# Andonstar_LED_Ring.net
KiCad netlist of a schematic drawn in EAGLE
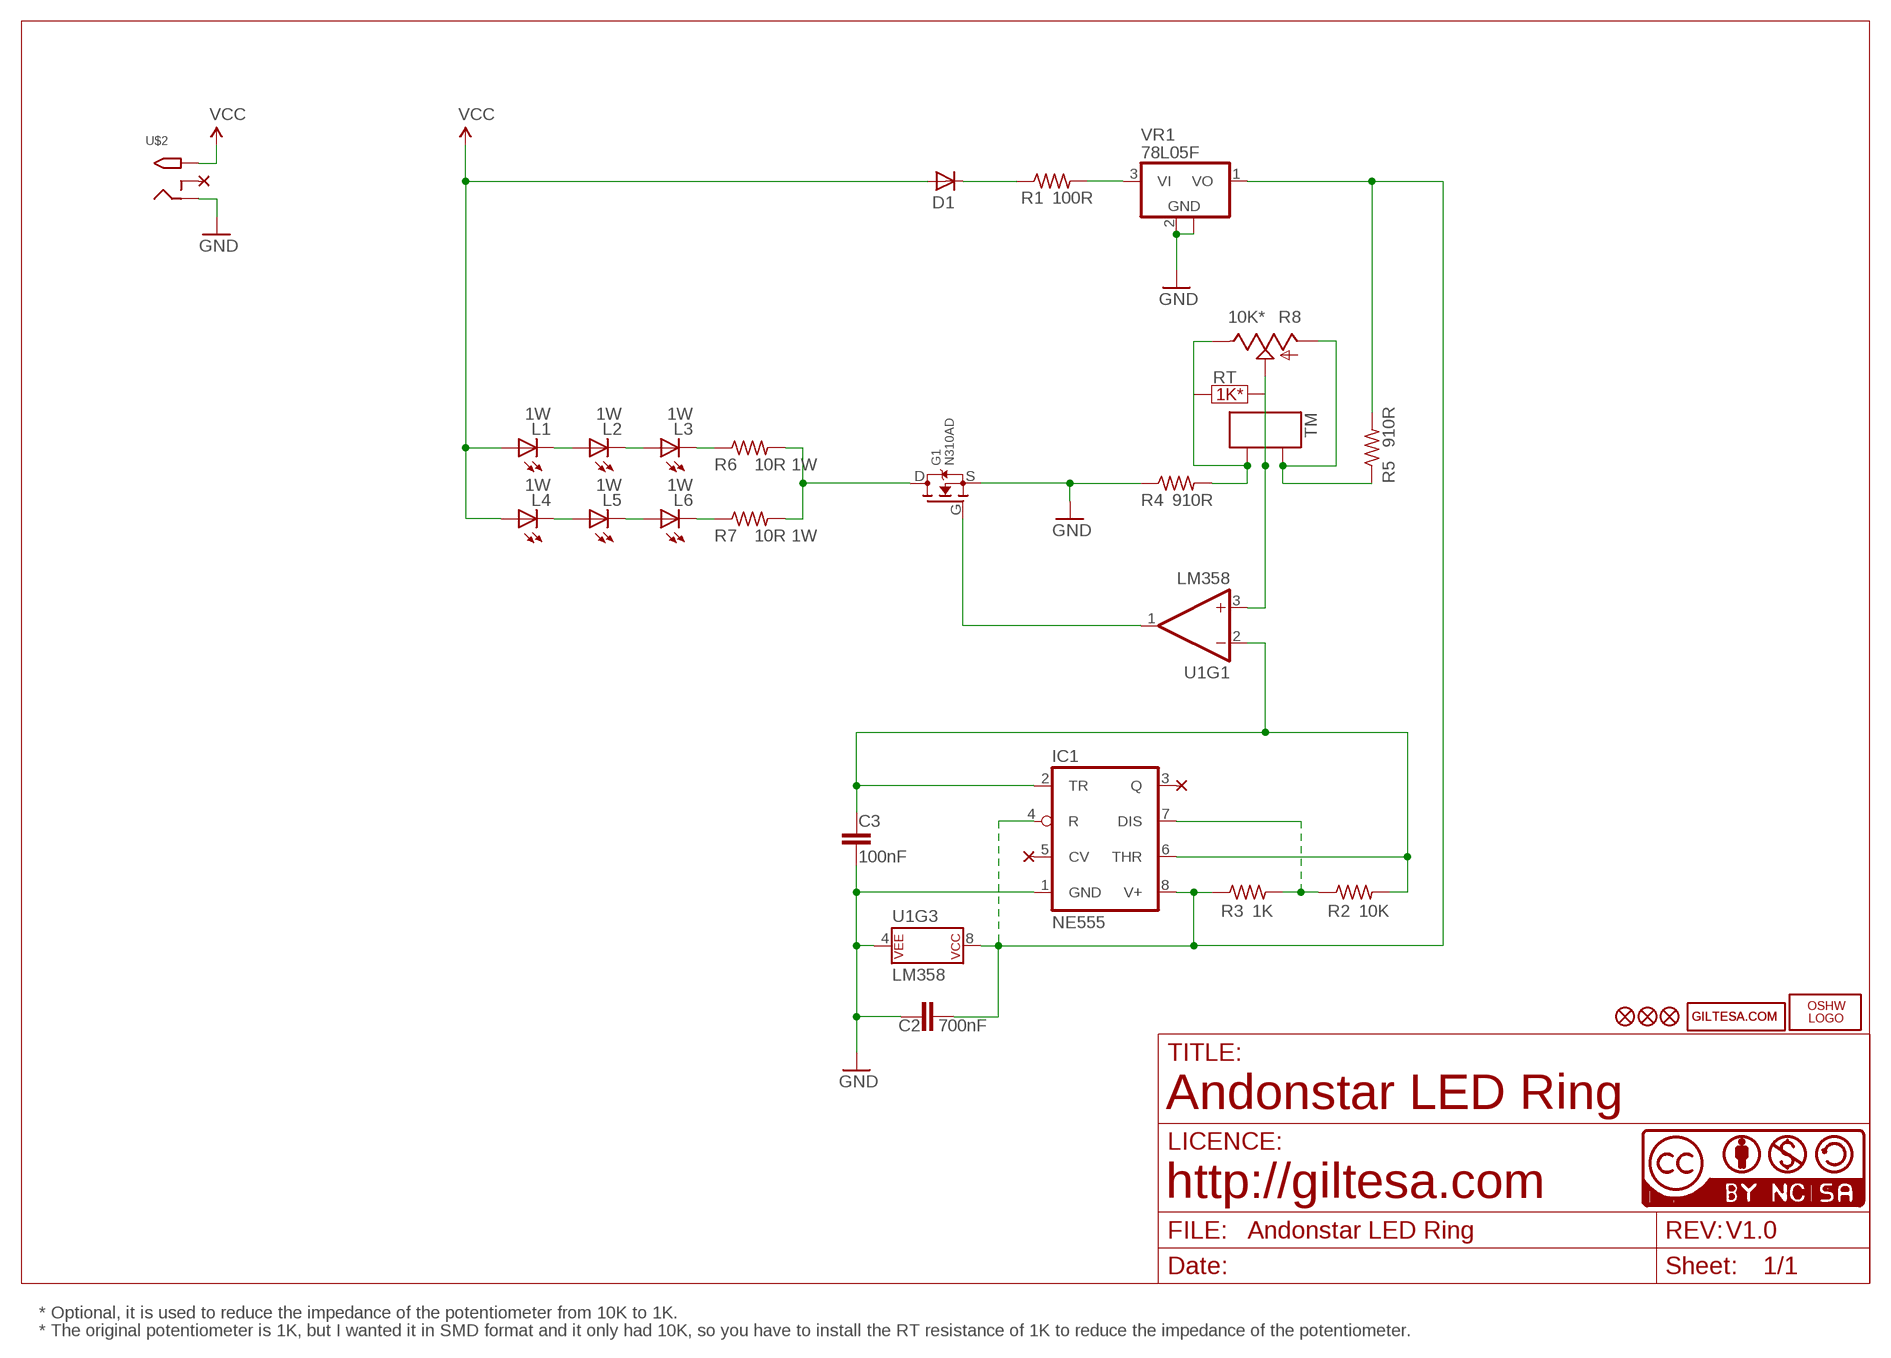
[diagram p0: schematic, sheet 1]

(export (version "E")
  (design (tool "Eeschema 10.0.6"))
  (components
    (comp (ref "C2")
      (value "700nF")
      (footprint "eagle-import:C0603")
      (libsource (lib "eagle-import") (part "C0603"))
    )
    (comp (ref "C3")
      (value "100nF")
      (footprint "eagle-import:C0603")
      (libsource (lib "eagle-import") (part "C0603"))
    )
    (comp (ref "D1")
      (value "DIODE-GF1")
      (footprint "eagle-import:GF1")
      (libsource (lib "eagle-import") (part "DIODE-GF1"))
    )
    (comp (ref "G1")
      (value "N310AD")
      (footprint "eagle-import:TO-252")
      (libsource (lib "eagle-import") (part "FDD8447L"))
    )
    (comp (ref "IC1")
      (value "NE555")
      (footprint "eagle-import:SO08")
      (libsource (lib "eagle-import") (part "555DNE"))
    )
    (comp (ref "L1")
      (value "1W")
      (footprint "eagle-import:LED_Z_POWER")
      (libsource (lib "eagle-import") (part "LED_Z_POWER"))
    )
    (comp (ref "L2")
      (value "1W")
      (footprint "eagle-import:LED_Z_POWER")
      (libsource (lib "eagle-import") (part "LED_Z_POWER"))
    )
    (comp (ref "L3")
      (value "1W")
      (footprint "eagle-import:LED_Z_POWER")
      (libsource (lib "eagle-import") (part "LED_Z_POWER"))
    )
    (comp (ref "L4")
      (value "1W")
      (footprint "eagle-import:LED_Z_POWER")
      (libsource (lib "eagle-import") (part "LED_Z_POWER"))
    )
    (comp (ref "L5")
      (value "1W")
      (footprint "eagle-import:LED_Z_POWER")
      (libsource (lib "eagle-import") (part "LED_Z_POWER"))
    )
    (comp (ref "L6")
      (value "1W")
      (footprint "eagle-import:LED_Z_POWER")
      (libsource (lib "eagle-import") (part "LED_Z_POWER"))
    )
    (comp (ref "LOGO1")
      (value "OSHW_LOGO_FILLX0150-NT")
      (footprint "eagle-import:OSHW_FILLX150_NOTEXT")
      (libsource (lib "eagle-import") (part "OSHW_LOGO_FILLX0150-NT"))
    )
    (comp (ref "R1")
      (value "100R")
      (footprint "eagle-import:R1206")
      (libsource (lib "eagle-import") (part "R1206"))
    )
    (comp (ref "R2")
      (value "10K")
      (footprint "eagle-import:R0603")
      (libsource (lib "eagle-import") (part "R0603"))
    )
    (comp (ref "R3")
      (value "1K")
      (footprint "eagle-import:R0603")
      (libsource (lib "eagle-import") (part "R0603"))
    )
    (comp (ref "R4")
      (value "910R")
      (footprint "eagle-import:R0603")
      (libsource (lib "eagle-import") (part "R0603"))
    )
    (comp (ref "R5")
      (value "910R")
      (footprint "eagle-import:R0603")
      (libsource (lib "eagle-import") (part "R0603"))
    )
    (comp (ref "R6")
      (value "10R 1W")
      (footprint "eagle-import:R2512")
      (libsource (lib "eagle-import") (part "R-US_R2512"))
    )
    (comp (ref "R7")
      (value "10R 1W")
      (footprint "eagle-import:R2512")
      (libsource (lib "eagle-import") (part "R-US_R2512"))
    )
    (comp (ref "R8")
      (value "10K*")
      (footprint "eagle-import:TRIMPOT_SMD_16MM")
      (libsource (lib "eagle-import") (part "TRIMPOT_16MM_SMD"))
    )
    (comp (ref "TM")
      (value "1X03")
      (footprint "eagle-import:1X03_SMD")
      (libsource (lib "eagle-import") (part "1X03"))
    )
    (comp (ref "U$1")
      (value "GILTESA.COM_MASK")
      (footprint "eagle-import:GILTESA.COM_MASK")
      (libsource (lib "eagle-import") (part "GILTESA.COM_MASK"))
    )
    (comp (ref "U$2")
      (value "2.1MMJACKSMT")
      (footprint "eagle-import:DCJACK_2MM_SMT")
      (libsource (lib "eagle-import") (part "2.1MMJACKSMT"))
    )
    (comp (ref "U$6")
      (value "FIDUCIAL1X2")
      (footprint "eagle-import:FIDUCIAL-1X2")
      (libsource (lib "eagle-import") (part "FIDUCIAL1X2"))
    )
    (comp (ref "U$7")
      (value "FIDUCIAL1X2")
      (footprint "eagle-import:FIDUCIAL-1X2")
      (libsource (lib "eagle-import") (part "FIDUCIAL1X2"))
    )
    (comp (ref "U$8")
      (value "GILTESA.COM_COPPER_STOP")
      (footprint "eagle-import:GILTESA.COM_COPPER_STOP")
      (libsource (lib "eagle-import") (part "GILTESA.COM_COPPER_STOP"))
    )
    (comp (ref "U$14")
      (value "FIDUCIAL1X2")
      (footprint "eagle-import:FIDUCIAL-1X2")
      (libsource (lib "eagle-import") (part "FIDUCIAL1X2"))
    )
    (comp (ref "U$20")
      (value "CC-NC-BCNIX")
      (footprint "eagle-import:CC-NC-B_NIX")
      (libsource (lib "eagle-import") (part "CC-NC-BCNIX"))
    )
    (comp (ref "U1")
      (value "LM358")
      (footprint "eagle-import:SO08")
      (libsource (lib "eagle-import") (part "LM358"))
    )
    (comp (ref "VR1")
      (value "78L05F")
      (footprint "eagle-import:SOT89")
      (libsource (lib "eagle-import") (part "78LF05"))
    )
  )
  (nets
    (net (code "1") (name "GND") (class "Default")
      (node (ref "C2") (pin "2") (pinfunction "2_2") (pintype "passive"))
      (node (ref "C3") (pin "1") (pinfunction "1_1") (pintype "passive"))
      (node (ref "G1") (pin "S") (pinfunction "S_S") (pintype "bidirectional"))
      (node (ref "IC1") (pin "1") (pinfunction "GND_1") (pintype "power_in"))
      (node (ref "R4") (pin "1") (pinfunction "1_1") (pintype "passive"))
      (node (ref "U$2") (pin "GND") (pinfunction "RING_GND") (pintype "bidirectional"))
      (node (ref "U1") (pin "4") (pinfunction "P$V-_4") (pintype "bidirectional"))
      (node (ref "VR1") (pin "2") (pinfunction "GND_2") (pintype "passive"))
      (node (ref "VR1") (pin "2@1") (pinfunction "GND_2@1") (pintype "passive"))
    )
    (net (code "2") (name "Net-(D1-PadC)") (class "Default")
      (node (ref "D1") (pin "C") (pinfunction "C_C") (pintype "passive"))
      (node (ref "R1") (pin "1") (pinfunction "1_1") (pintype "passive"))
    )
    (net (code "3") (name "Net-(G1-PadD)") (class "Default")
      (node (ref "G1") (pin "D") (pinfunction "D_D") (pintype "bidirectional"))
      (node (ref "R6") (pin "2") (pinfunction "2_2") (pintype "passive"))
      (node (ref "R7") (pin "2") (pinfunction "2_2") (pintype "passive"))
    )
    (net (code "4") (name "Net-(IC1-DIS)") (class "Default")
      (node (ref "IC1") (pin "7") (pinfunction "DIS_7") (pintype "input"))
      (node (ref "R2") (pin "1") (pinfunction "1_1") (pintype "passive"))
      (node (ref "R3") (pin "2") (pinfunction "2_2") (pintype "passive"))
    )
    (net (code "5") (name "Net-(IC1-R)") (class "Default")
      (node (ref "C2") (pin "1") (pinfunction "1_1") (pintype "passive"))
      (node (ref "IC1") (pin "4") (pinfunction "R_4") (pintype "input"))
      (node (ref "IC1") (pin "8") (pinfunction "V+_8") (pintype "power_in"))
      (node (ref "R3") (pin "1") (pinfunction "1_1") (pintype "passive"))
      (node (ref "R5") (pin "2") (pinfunction "2_2") (pintype "passive"))
      (node (ref "U1") (pin "8") (pinfunction "P$V+_8") (pintype "bidirectional"))
      (node (ref "VR1") (pin "1") (pinfunction "VO_1") (pintype "passive"))
    )
    (net (code "6") (name "Net-(IC1-THR)") (class "Default")
      (node (ref "C3") (pin "2") (pinfunction "2_2") (pintype "passive"))
      (node (ref "IC1") (pin "2") (pinfunction "TR_2") (pintype "input"))
      (node (ref "IC1") (pin "6") (pinfunction "THR_6") (pintype "input"))
      (node (ref "R2") (pin "2") (pinfunction "2_2") (pintype "passive"))
      (node (ref "U1") (pin "2") (pinfunction "-IN_2") (pintype "input"))
    )
    (net (code "7") (name "Net-(L1-PadC)") (class "Default")
      (node (ref "L1") (pin "C") (pinfunction "C_C") (pintype "passive"))
      (node (ref "L2") (pin "A") (pinfunction "A_A") (pintype "passive"))
    )
    (net (code "8") (name "Net-(L2-PadC)") (class "Default")
      (node (ref "L2") (pin "C") (pinfunction "C_C") (pintype "passive"))
      (node (ref "L3") (pin "A") (pinfunction "A_A") (pintype "passive"))
    )
    (net (code "9") (name "Net-(L3-PadC)") (class "Default")
      (node (ref "L3") (pin "C") (pinfunction "C_C") (pintype "passive"))
      (node (ref "R6") (pin "1") (pinfunction "1_1") (pintype "passive"))
    )
    (net (code "10") (name "Net-(L4-PadC)") (class "Default")
      (node (ref "L4") (pin "C") (pinfunction "C_C") (pintype "passive"))
      (node (ref "L5") (pin "A") (pinfunction "A_A") (pintype "passive"))
    )
    (net (code "11") (name "Net-(L5-PadC)") (class "Default")
      (node (ref "L5") (pin "C") (pinfunction "C_C") (pintype "passive"))
      (node (ref "L6") (pin "A") (pinfunction "A_A") (pintype "passive"))
    )
    (net (code "12") (name "Net-(L6-PadC)") (class "Default")
      (node (ref "L6") (pin "C") (pinfunction "C_C") (pintype "passive"))
      (node (ref "R7") (pin "1") (pinfunction "1_1") (pintype "passive"))
    )
    (net (code "13") (name "Net-(R4-Pad2)") (class "Default")
      (node (ref "R4") (pin "2") (pinfunction "2_2") (pintype "passive"))
      (node (ref "R8") (pin "B") (pinfunction "B_B") (pintype "passive"))
      (node (ref "TM") (pin "1") (pinfunction "1_1") (pintype "passive"))
    )
    (net (code "14") (name "Net-(R5-Pad1)") (class "Default")
      (node (ref "R5") (pin "1") (pinfunction "1_1") (pintype "passive"))
      (node (ref "R8") (pin "A") (pinfunction "A_A") (pintype "passive"))
      (node (ref "TM") (pin "3") (pinfunction "3_3") (pintype "passive"))
    )
    (net (code "15") (name "Net-(U1A-+IN)") (class "Default")
      (node (ref "R8") (pin "S") (pinfunction "S_S") (pintype "passive"))
      (node (ref "TM") (pin "2") (pinfunction "2_2") (pintype "passive"))
      (node (ref "U1") (pin "3") (pinfunction "+IN_3") (pintype "input"))
    )
    (net (code "16") (name "Net-(U1A-OUT)") (class "Default")
      (node (ref "G1") (pin "G") (pinfunction "G_G") (pintype "bidirectional"))
      (node (ref "U1") (pin "1") (pinfunction "OUT_1") (pintype "output"))
    )
    (net (code "17") (name "Net-(VR1-VI)") (class "Default")
      (node (ref "R1") (pin "2") (pinfunction "2_2") (pintype "passive"))
      (node (ref "VR1") (pin "3") (pinfunction "VI_3") (pintype "input"))
    )
    (net (code "18") (name "VCC") (class "Default")
      (node (ref "D1") (pin "A") (pinfunction "A_A") (pintype "passive"))
      (node (ref "L1") (pin "A") (pinfunction "A_A") (pintype "passive"))
      (node (ref "L4") (pin "A") (pinfunction "A_A") (pintype "passive"))
      (node (ref "U$2") (pin "PWR2") (pinfunction "TIP_PWR2") (pintype "bidirectional"))
    )
    (net (code "19") (name "unconnected-(IC1-CV-Pad5)") (class "Default")
      (node (ref "IC1") (pin "5") (pinfunction "CV_5") (pintype "input"))
    )
    (net (code "20") (name "unconnected-(IC1-Q-Pad3)") (class "Default")
      (node (ref "IC1") (pin "3") (pinfunction "Q_3") (pintype "output"))
    )
    (net (code "21") (name "unconnected-(U$2-RING_SW-PadGNDBREAK)") (class "Default")
      (node (ref "U$2") (pin "GNDBREAK") (pinfunction "RING_SW_GNDBREAK") (pintype "bidirectional"))
    )
  )
)
